# controller.net
KiCad netlist of a schematic drawn in Altium Designer
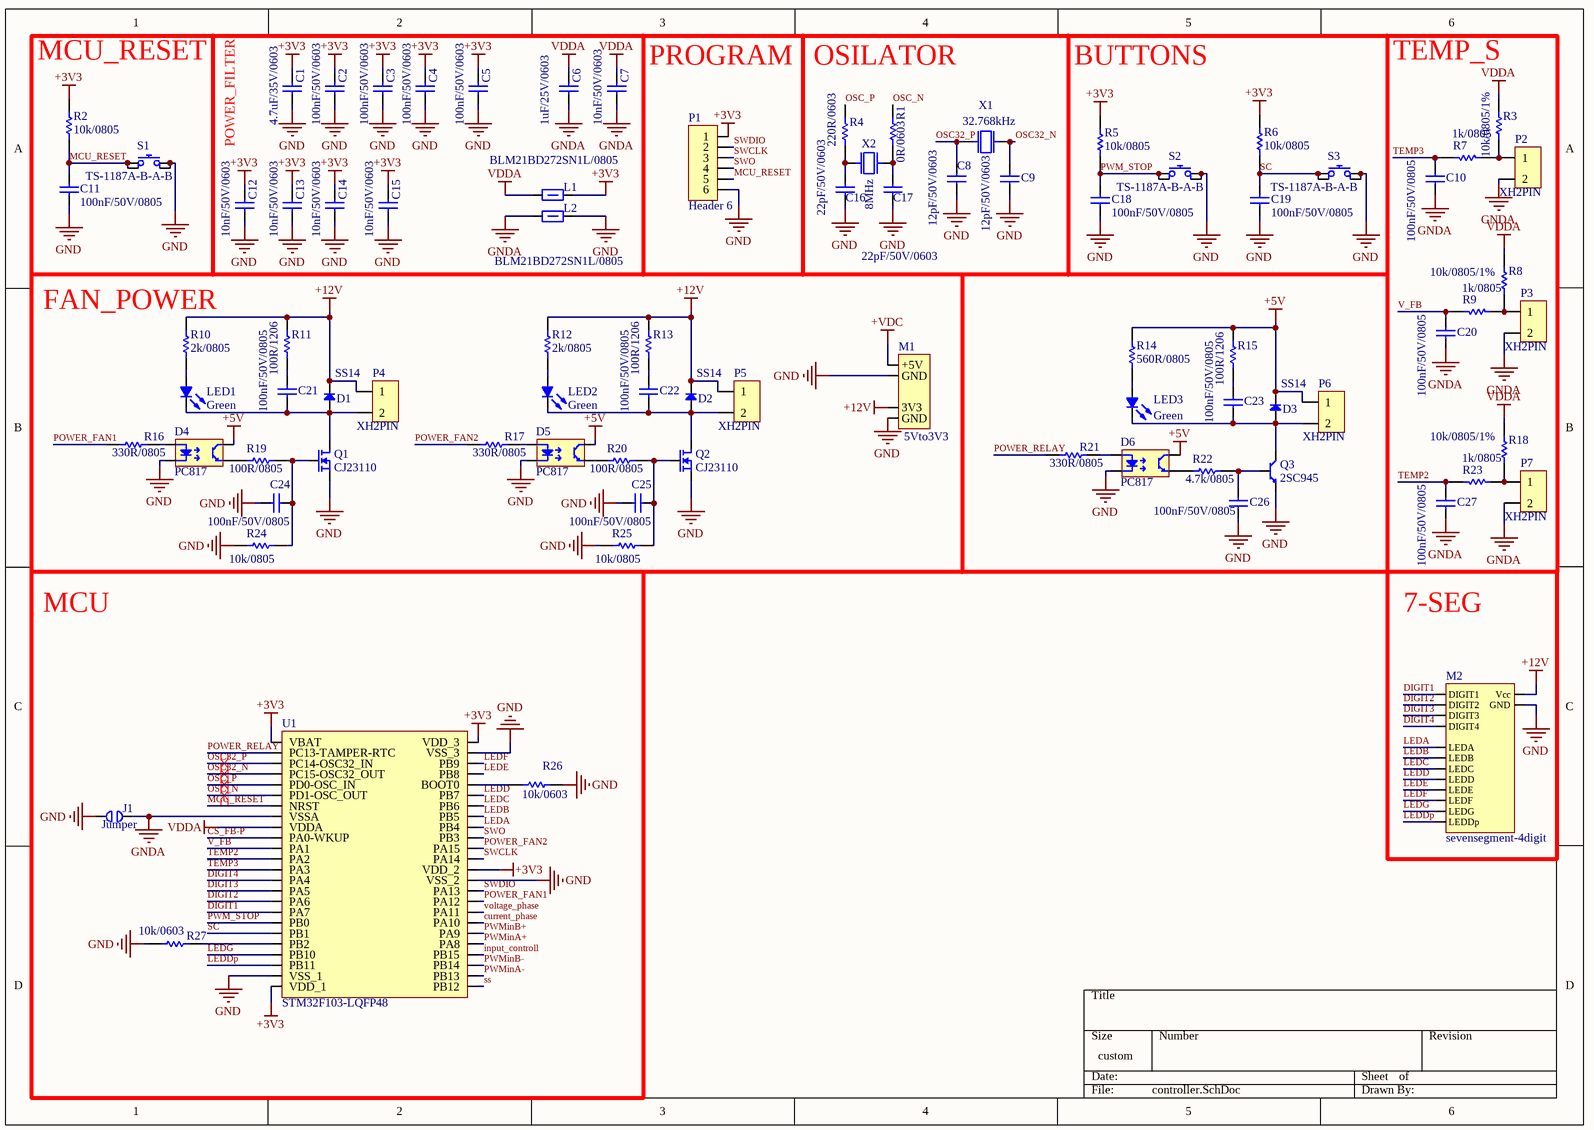
[diagram p0: controller.SchDoc]

(export (version "E")
  (design (tool "Eeschema 10.0.6"))
  (components
    (comp (ref "C1")
      (value "4.7uF/35V/0603")
      (footprint "cap 0603")
      (description "Capacitor")
      (libsource (lib "Schlib") (part "Capacitor"))
    )
    (comp (ref "C2")
      (value "100nF/50V/0603")
      (footprint "cap 0603")
      (description "Capacitor")
      (libsource (lib "Schlib") (part "Capacitor"))
    )
    (comp (ref "C3")
      (value "100nF/50V/0603")
      (footprint "cap 0603")
      (description "Capacitor")
      (libsource (lib "Schlib") (part "Capacitor"))
    )
    (comp (ref "C4")
      (value "100nF/50V/0603")
      (footprint "cap 0603")
      (description "Capacitor")
      (libsource (lib "Schlib") (part "Capacitor"))
    )
    (comp (ref "C5")
      (value "100nF/50V/0603")
      (footprint "cap 0603")
      (description "Capacitor")
      (libsource (lib "Schlib") (part "Capacitor"))
    )
    (comp (ref "C6")
      (value "1uF/25V/0603")
      (footprint "cap 0603")
      (description "Capacitor")
      (libsource (lib "Schlib") (part "Capacitor"))
    )
    (comp (ref "C7")
      (value "10nF/50V/0603")
      (footprint "cap 0603")
      (description "Capacitor")
      (libsource (lib "Schlib") (part "Capacitor"))
    )
    (comp (ref "C8")
      (value "12pF/50V/0603")
      (footprint "cap 0603")
      (description "Capacitor")
      (libsource (lib "Schlib") (part "Capacitor"))
    )
    (comp (ref "C9")
      (value "12pF/50V/0603")
      (footprint "cap 0603")
      (description "Capacitor")
      (libsource (lib "Schlib") (part "Capacitor"))
    )
    (comp (ref "C10")
      (value "100nF/50V/0805")
      (footprint "CAP 0805")
      (description "Capacitor")
      (libsource (lib "Schlib") (part "Capacitor"))
    )
    (comp (ref "C11")
      (value "100nF/50V/0805")
      (footprint "CAP 0805")
      (description "Capacitor")
      (libsource (lib "Schlib") (part "Capacitor"))
    )
    (comp (ref "C12")
      (value "10nF/50V/0603")
      (footprint "cap 0603")
      (description "Capacitor")
      (libsource (lib "Schlib") (part "Capacitor"))
    )
    (comp (ref "C13")
      (value "10nF/50V/0603")
      (footprint "cap 0603")
      (description "Capacitor")
      (libsource (lib "Schlib") (part "Capacitor"))
    )
    (comp (ref "C14")
      (value "10nF/50V/0603")
      (footprint "cap 0603")
      (description "Capacitor")
      (libsource (lib "Schlib") (part "Capacitor"))
    )
    (comp (ref "C15")
      (value "10nF/50V/0603")
      (footprint "cap 0603")
      (description "Capacitor")
      (libsource (lib "Schlib") (part "Capacitor"))
    )
    (comp (ref "C16")
      (value "22pF/50V/0603")
      (footprint "cap 0603")
      (description "Capacitor")
      (libsource (lib "Schlib") (part "Capacitor"))
    )
    (comp (ref "C17")
      (value "22pF/50V/0603")
      (footprint "cap 0603")
      (description "Capacitor")
      (libsource (lib "Schlib") (part "Capacitor"))
    )
    (comp (ref "C18")
      (value "100nF/50V/0805")
      (footprint "CAP 0805")
      (description "Capacitor")
      (libsource (lib "Schlib") (part "Capacitor"))
    )
    (comp (ref "C19")
      (value "100nF/50V/0805")
      (footprint "CAP 0805")
      (description "Capacitor")
      (libsource (lib "Schlib") (part "Capacitor"))
    )
    (comp (ref "C20")
      (value "100nF/50V/0805")
      (footprint "CAP 0805")
      (description "Capacitor")
      (libsource (lib "Schlib") (part "Capacitor"))
    )
    (comp (ref "C21")
      (value "100nF/50V/0805")
      (footprint "CAP 0805")
      (description "Capacitor")
      (libsource (lib "Schlib") (part "Capacitor"))
    )
    (comp (ref "C22")
      (value "100nF/50V/0805")
      (footprint "CAP 0805")
      (description "Capacitor")
      (libsource (lib "Schlib") (part "Capacitor"))
    )
    (comp (ref "C23")
      (value "100nF/50V/0805")
      (footprint "CAP 0805")
      (description "Capacitor")
      (libsource (lib "Schlib") (part "Capacitor"))
    )
    (comp (ref "C24")
      (value "100nF/50V/0805")
      (footprint "CAP 0805")
      (description "Capacitor")
      (libsource (lib "Schlib") (part "Capacitor"))
    )
    (comp (ref "C25")
      (value "100nF/50V/0805")
      (footprint "CAP 0805")
      (description "Capacitor")
      (libsource (lib "Schlib") (part "Capacitor"))
    )
    (comp (ref "C26")
      (value "100nF/50V/0805")
      (footprint "CAP 0805")
      (description "Capacitor")
      (libsource (lib "Schlib") (part "Capacitor"))
    )
    (comp (ref "C27")
      (value "100nF/50V/0805")
      (footprint "CAP 0805")
      (description "Capacitor")
      (libsource (lib "Schlib") (part "Capacitor"))
    )
    (comp (ref "D1") (value "SS14") (footprint "SMA") (libsource (lib "Schlib") (part "Diode")))
    (comp (ref "D2") (value "SS14") (footprint "SMA") (libsource (lib "Schlib") (part "Diode")))
    (comp (ref "D3") (value "SS14") (footprint "SMA") (libsource (lib "Schlib") (part "Diode")))
    (comp (ref "D4") (value "PC817") (footprint "pc817") (libsource (lib "Schlib") (part "PC817")))
    (comp (ref "D5") (value "PC817") (footprint "pc817") (libsource (lib "Schlib") (part "PC817")))
    (comp (ref "D6") (value "PC817") (footprint "pc817") (libsource (lib "Schlib") (part "PC817")))
    (comp (ref "J1") (value "Jumper") (footprint "pin-header 2*1") (libsource (lib "Schlib") (part "Jumper")))
    (comp (ref "L1")
      (value "BLM21BD272SN1L/0805")
      (footprint "RES 0805")
      (libsource (lib "Schlib") (part "Ferrite Bead"))
    )
    (comp (ref "L2")
      (value "BLM21BD272SN1L/0805")
      (footprint "RES 0805")
      (libsource (lib "Schlib") (part "Ferrite Bead"))
    )
    (comp (ref "LED1")
      (value "LED 3mm/Green")
      (footprint "LED 3mm")
      (description "Typical LED")
      (fields (field (name "COLOR") "Green"))
      (libsource (lib "TL494 12V-20A-KARA") (part "LED"))
    )
    (comp (ref "LED2")
      (value "LED 3mm/Green")
      (footprint "LED 3mm")
      (description "Typical LED")
      (fields (field (name "COLOR") "Green"))
      (libsource (lib "TL494 12V-20A-KARA") (part "LED"))
    )
    (comp (ref "LED3")
      (value "LED 3mm/Green")
      (footprint "LED 3mm")
      (description "Typical LED")
      (fields (field (name "COLOR") "Green"))
      (libsource (lib "TL494 12V-20A-KARA") (part "LED"))
    )
    (comp (ref "M1") (value "5Vto3V3") (footprint "5Vto3V3") (libsource (lib "Schlib") (part "5Vto3V3")))
    (comp (ref "M2")
      (value "sevensegment-4digit")
      (footprint "7-SEG-BOARD")
      (libsource (lib "Schlib") (part "sevensegment-4digit"))
    )
    (comp (ref "P1")
      (value "Header 6")
      (footprint "pin-header 6*1")
      (libsource (lib "Schlib") (part "Header 6"))
    )
    (comp (ref "P2")
      (value "XH2PIN")
      (footprint "XH-2Pin")
      (description "RELAY")
      (fields (field (name "PUBLISHER") "Altium Limited"))
      (libsource (lib "Schlib") (part "Header 2H"))
    )
    (comp (ref "P3")
      (value "XH2PIN")
      (footprint "XH-2Pin")
      (description "RELAY")
      (fields (field (name "PUBLISHER") "Altium Limited"))
      (libsource (lib "Schlib") (part "Header 2H"))
    )
    (comp (ref "P4")
      (value "XH2PIN")
      (footprint "XH-2Pin")
      (description "RELAY")
      (fields (field (name "PUBLISHER") "Altium Limited"))
      (libsource (lib "Schlib") (part "Header 2H"))
    )
    (comp (ref "P5")
      (value "XH2PIN")
      (footprint "XH-2Pin")
      (description "RELAY")
      (fields (field (name "PUBLISHER") "Altium Limited"))
      (libsource (lib "Schlib") (part "Header 2H"))
    )
    (comp (ref "P6")
      (value "XH2PIN")
      (footprint "pin-header 2*1")
      (description "RELAY")
      (fields (field (name "PUBLISHER") "Altium Limited"))
      (libsource (lib "Schlib") (part "Header 2H"))
    )
    (comp (ref "P7")
      (value "XH2PIN")
      (footprint "XH-2Pin")
      (description "RELAY")
      (fields (field (name "PUBLISHER") "Altium Limited"))
      (libsource (lib "Schlib") (part "Header 2H"))
    )
    (comp (ref "Q1")
      (value "CJ23110")
      (footprint "SOT-23")
      (libsource (lib "Schlib") (part "Mosfet N-channel"))
    )
    (comp (ref "Q2")
      (value "CJ23110")
      (footprint "SOT-23")
      (libsource (lib "Schlib") (part "Mosfet N-channel"))
    )
    (comp (ref "Q3") (value "2SC945") (footprint "SOT-23") (libsource (lib "Schlib") (part "BJT-NPN")))
    (comp (ref "R1") (value "0R/0603") (footprint "Resistor 0603") (libsource (lib "22") (part "Res 0.5 W")))
    (comp (ref "R2") (value "10k/0805") (footprint "RES 0805") (libsource (lib "22") (part "Res 0.5 W")))
    (comp (ref "R3") (value "10k/0805/1%") (footprint "RES 0805") (libsource (lib "22") (part "Res 0.5 W")))
    (comp (ref "R4")
      (value "220R/0603")
      (footprint "Resistor 0603")
      (libsource (lib "22") (part "Res 0.5 W"))
    )
    (comp (ref "R5") (value "10k/0805") (footprint "RES 0805") (libsource (lib "22") (part "Res 0.5 W")))
    (comp (ref "R6") (value "10k/0805") (footprint "RES 0805") (libsource (lib "22") (part "Res 0.5 W")))
    (comp (ref "R7")
      (value "1k/0805")
      (footprint "RES 0805")
      (description "Resistor")
      (fields (field (name "PUBLISHER") "Altium Limited"))
      (libsource (lib "Miscellaneous Devices") (part "Res1"))
    )
    (comp (ref "R8") (value "10k/0805/1%") (footprint "RES 0805") (libsource (lib "22") (part "Res 0.5 W")))
    (comp (ref "R9")
      (value "1k/0805")
      (footprint "RES 0805")
      (description "Resistor")
      (fields (field (name "PUBLISHER") "Altium Limited"))
      (libsource (lib "Miscellaneous Devices") (part "Res1"))
    )
    (comp (ref "R10") (value "2k/0805") (footprint "RES 0805") (libsource (lib "Schlib") (part "Res")))
    (comp (ref "R11") (value "100R/1206") (footprint "RES 1206") (libsource (lib "22") (part "Res 0.5 W")))
    (comp (ref "R12") (value "2k/0805") (footprint "RES 0805") (libsource (lib "Schlib") (part "Res")))
    (comp (ref "R13") (value "100R/1206") (footprint "RES 1206") (libsource (lib "22") (part "Res 0.5 W")))
    (comp (ref "R14") (value "560R/0805") (footprint "RES 0805") (libsource (lib "Schlib") (part "Res")))
    (comp (ref "R15") (value "100R/1206") (footprint "RES 1206") (libsource (lib "22") (part "Res 0.5 W")))
    (comp (ref "R16") (value "330R/0805") (footprint "RES 0805") (libsource (lib "22") (part "Res 0.5 W")))
    (comp (ref "R17") (value "330R/0805") (footprint "RES 0805") (libsource (lib "22") (part "Res 0.5 W")))
    (comp (ref "R18") (value "10k/0805/1%") (footprint "RES 0805") (libsource (lib "22") (part "Res 0.5 W")))
    (comp (ref "R19") (value "100R/0805") (footprint "RES 0805") (libsource (lib "22") (part "Res 0.5 W")))
    (comp (ref "R20") (value "100R/0805") (footprint "RES 0805") (libsource (lib "22") (part "Res 0.5 W")))
    (comp (ref "R21") (value "330R/0805") (footprint "RES 0805") (libsource (lib "22") (part "Res 0.5 W")))
    (comp (ref "R22") (value "4.7k/0805") (footprint "RES 0805") (libsource (lib "22") (part "Res 0.5 W")))
    (comp (ref "R23")
      (value "1k/0805")
      (footprint "RES 0805")
      (description "Resistor")
      (fields (field (name "PUBLISHER") "Altium Limited"))
      (libsource (lib "Miscellaneous Devices") (part "Res1"))
    )
    (comp (ref "R24") (value "10k/0805") (footprint "RES 0805") (libsource (lib "22") (part "Res 0.5 W")))
    (comp (ref "R25") (value "10k/0805") (footprint "RES 0805") (libsource (lib "22") (part "Res 0.5 W")))
    (comp (ref "R26")
      (value "10k/0603")
      (footprint "Resistor 0603")
      (libsource (lib "22") (part "Res 0.5 W"))
    )
    (comp (ref "R27")
      (value "10k/0603")
      (footprint "Resistor 0603")
      (libsource (lib "22") (part "Res 0.5 W"))
    )
    (comp (ref "S1")
      (value "TS-1187A-B-A-B")
      (footprint "TS-1187A-B-A-B(push button)")
      (libsource (lib "Schlib") (part "push button"))
    )
    (comp (ref "S2")
      (value "TS-1187A-B-A-B")
      (footprint "TS-1187A-B-A-B(push button)")
      (libsource (lib "Schlib") (part "push button"))
    )
    (comp (ref "S3")
      (value "TS-1187A-B-A-B")
      (footprint "TS-1187A-B-A-B(push button)")
      (libsource (lib "Schlib") (part "push button"))
    )
    (comp (ref "U1")
      (value "STM32F103-LQFP48")
      (footprint "LQFP48")
      (libsource (lib "Schlib") (part "STM32F103C8T6"))
    )
    (comp (ref "X1")
      (value "32.768kHz")
      (footprint "CRYSTAL(32.768)-SMD")
      (libsource (lib "Schlib") (part "crystal"))
    )
    (comp (ref "X2") (value "8MHz") (footprint "crystal(8M)-smd") (libsource (lib "Schlib") (part "crystal")))
  )
  (nets
    (net (code "1") (name "+3V3") (class "Default")
      (node (ref "C1") (pin "1") (pinfunction "+_1") (pintype "passive"))
      (node (ref "C12") (pin "2") (pinfunction "-_2") (pintype "passive"))
      (node (ref "C13") (pin "2") (pinfunction "-_2") (pintype "passive"))
      (node (ref "C14") (pin "1") (pinfunction "+_1") (pintype "passive"))
      (node (ref "C15") (pin "2") (pinfunction "-_2") (pintype "passive"))
      (node (ref "C2") (pin "2") (pinfunction "-_2") (pintype "passive"))
      (node (ref "C3") (pin "2") (pinfunction "-_2") (pintype "passive"))
      (node (ref "C4") (pin "1") (pinfunction "+_1") (pintype "passive"))
      (node (ref "C5") (pin "2") (pinfunction "-_2") (pintype "passive"))
      (node (ref "L1") (pin "2") (pinfunction "2_2") (pintype "passive"))
      (node (ref "P1") (pin "1") (pinfunction "1_1") (pintype "passive"))
      (node (ref "R2") (pin "1") (pinfunction "1_1") (pintype "passive"))
      (node (ref "R5") (pin "1") (pinfunction "1_1") (pintype "passive"))
      (node (ref "R6") (pin "1") (pinfunction "1_1") (pintype "passive"))
      (node (ref "U1") (pin "1") (pinfunction "VBAT_1") (pintype "passive"))
      (node (ref "U1") (pin "24") (pinfunction "VDD_1_24") (pintype "passive"))
      (node (ref "U1") (pin "36") (pinfunction "VDD_2_36") (pintype "passive"))
      (node (ref "U1") (pin "48") (pinfunction "VDD_3_48") (pintype "passive"))
    )
    (net (code "2") (name "+5V") (class "Default")
      (node (ref "D3") (pin "2") (pinfunction "2_2") (pintype "passive"))
      (node (ref "D4") (pin "4") (pinfunction "Collector_4") (pintype "passive"))
      (node (ref "D5") (pin "4") (pinfunction "Collector_4") (pintype "passive"))
      (node (ref "D6") (pin "4") (pinfunction "Collector_4") (pintype "passive"))
      (node (ref "P6") (pin "1") (pinfunction "1_1") (pintype "passive"))
      (node (ref "R14") (pin "2") (pinfunction "2_2") (pintype "passive"))
      (node (ref "R15") (pin "1") (pinfunction "1_1") (pintype "passive"))
    )
    (net (code "3") (name "+12V") (class "Default")
      (node (ref "D1") (pin "2") (pinfunction "2_2") (pintype "passive"))
      (node (ref "D2") (pin "2") (pinfunction "2_2") (pintype "passive"))
      (node (ref "M1") (pin "3") (pinfunction "3V3_3") (pintype "passive"))
      (node (ref "M2") (pin "13") (pinfunction "Vcc_13") (pintype "passive"))
      (node (ref "P4") (pin "1") (pinfunction "1_1") (pintype "passive"))
      (node (ref "P5") (pin "1") (pinfunction "1_1") (pintype "passive"))
      (node (ref "R10") (pin "2") (pinfunction "2_2") (pintype "passive"))
      (node (ref "R11") (pin "1") (pinfunction "1_1") (pintype "passive"))
      (node (ref "R12") (pin "2") (pinfunction "2_2") (pintype "passive"))
      (node (ref "R13") (pin "1") (pinfunction "1_1") (pintype "passive"))
    )
    (net (code "4") (name "+VDC") (class "Default")
      (node (ref "M1") (pin "1") (pinfunction "+5V_1") (pintype "passive"))
    )
    (net (code "5") (name "/CS_FB-P") (class "Default")
      (node (ref "U1") (pin "10") (pinfunction "PA0-WKUP_10") (pintype "passive"))
    )
    (net (code "6") (name "/DIGIT1") (class "Default")
      (node (ref "M2") (pin "1") (pinfunction "DIGIT1_1") (pintype "passive"))
      (node (ref "U1") (pin "17") (pinfunction "PA7_17") (pintype "passive"))
    )
    (net (code "7") (name "/DIGIT2") (class "Default")
      (node (ref "M2") (pin "2") (pinfunction "DIGIT2_2") (pintype "passive"))
      (node (ref "U1") (pin "16") (pinfunction "PA6_16") (pintype "passive"))
    )
    (net (code "8") (name "/DIGIT3") (class "Default")
      (node (ref "M2") (pin "3") (pinfunction "DIGIT3_3") (pintype "passive"))
      (node (ref "U1") (pin "15") (pinfunction "PA5_15") (pintype "passive"))
    )
    (net (code "9") (name "/DIGIT4") (class "Default")
      (node (ref "M2") (pin "4") (pinfunction "DIGIT4_4") (pintype "passive"))
      (node (ref "U1") (pin "14") (pinfunction "PA4_14") (pintype "passive"))
    )
    (net (code "10") (name "/LEDA") (class "Default")
      (node (ref "M2") (pin "5") (pinfunction "LEDA_5") (pintype "passive"))
      (node (ref "U1") (pin "40") (pinfunction "PB4_40") (pintype "passive"))
    )
    (net (code "11") (name "/LEDB") (class "Default")
      (node (ref "M2") (pin "6") (pinfunction "LEDB_6") (pintype "passive"))
      (node (ref "U1") (pin "41") (pinfunction "PB5_41") (pintype "passive"))
    )
    (net (code "12") (name "/LEDC") (class "Default")
      (node (ref "M2") (pin "7") (pinfunction "LEDC_7") (pintype "passive"))
      (node (ref "U1") (pin "42") (pinfunction "PB6_42") (pintype "passive"))
    )
    (net (code "13") (name "/LEDD") (class "Default")
      (node (ref "M2") (pin "8") (pinfunction "LEDD_8") (pintype "passive"))
      (node (ref "U1") (pin "43") (pinfunction "PB7_43") (pintype "passive"))
    )
    (net (code "14") (name "/LEDDp") (class "Default")
      (node (ref "M2") (pin "12") (pinfunction "LEDDp_12") (pintype "passive"))
      (node (ref "U1") (pin "22") (pinfunction "PB11_22") (pintype "passive"))
    )
    (net (code "15") (name "/LEDE") (class "Default")
      (node (ref "M2") (pin "9") (pinfunction "LEDE_9") (pintype "passive"))
      (node (ref "U1") (pin "45") (pinfunction "PB8_45") (pintype "passive"))
    )
    (net (code "16") (name "/LEDF") (class "Default")
      (node (ref "M2") (pin "10") (pinfunction "LEDF_10") (pintype "passive"))
      (node (ref "U1") (pin "46") (pinfunction "PB9_46") (pintype "passive"))
    )
    (net (code "17") (name "/LEDG") (class "Default")
      (node (ref "M2") (pin "11") (pinfunction "LEDG_11") (pintype "passive"))
      (node (ref "U1") (pin "21") (pinfunction "PB10_21") (pintype "passive"))
    )
    (net (code "18") (name "/MCU_RESET") (class "Default")
      (node (ref "C11") (pin "2") (pinfunction "-_2") (pintype "passive"))
      (node (ref "P1") (pin "5") (pinfunction "5_5") (pintype "passive"))
      (node (ref "R2") (pin "2") (pinfunction "2_2") (pintype "passive"))
      (node (ref "S1") (pin "1") (pinfunction "1_1") (pintype "passive"))
      (node (ref "S1") (pin "4") (pinfunction "4_4") (pintype "passive"))
      (node (ref "U1") (pin "7") (pinfunction "NRST_7") (pintype "passive"))
    )
    (net (code "19") (name "/OSC32_N") (class "Default")
      (node (ref "C9") (pin "2") (pinfunction "-_2") (pintype "passive"))
      (node (ref "U1") (pin "4") (pinfunction "PC15-OSC32_OUT_4") (pintype "passive"))
      (node (ref "X1") (pin "2") (pinfunction "2_2") (pintype "passive"))
    )
    (net (code "20") (name "/OSC32_P") (class "Default")
      (node (ref "C8") (pin "2") (pinfunction "-_2") (pintype "passive"))
      (node (ref "U1") (pin "3") (pinfunction "PC14-OSC32_IN_3") (pintype "passive"))
      (node (ref "X1") (pin "1") (pinfunction "1_1") (pintype "passive"))
    )
    (net (code "21") (name "/OSC_N") (class "Default")
      (node (ref "R1") (pin "1") (pinfunction "1_1") (pintype "passive"))
      (node (ref "U1") (pin "6") (pinfunction "PD1-OSC_OUT_6") (pintype "passive"))
    )
    (net (code "22") (name "/OSC_P") (class "Default")
      (node (ref "R4") (pin "1") (pinfunction "1_1") (pintype "passive"))
      (node (ref "U1") (pin "5") (pinfunction "PD0-OSC_IN_5") (pintype "passive"))
    )
    (net (code "23") (name "/POWER_FAN1") (class "Default")
      (node (ref "R16") (pin "2") (pinfunction "2_2") (pintype "passive"))
      (node (ref "U1") (pin "33") (pinfunction "PA12_33") (pintype "passive"))
    )
    (net (code "24") (name "/POWER_FAN2") (class "Default")
      (node (ref "R17") (pin "2") (pinfunction "2_2") (pintype "passive"))
      (node (ref "U1") (pin "38") (pinfunction "PA15_38") (pintype "passive"))
    )
    (net (code "25") (name "/POWER_RELAY") (class "Default")
      (node (ref "R21") (pin "2") (pinfunction "2_2") (pintype "passive"))
      (node (ref "U1") (pin "2") (pinfunction "PC13-TAMPER-RTC_2") (pintype "passive"))
    )
    (net (code "26") (name "/PWM_STOP") (class "Default")
      (node (ref "C18") (pin "2") (pinfunction "-_2") (pintype "passive"))
      (node (ref "R5") (pin "2") (pinfunction "2_2") (pintype "passive"))
      (node (ref "S2") (pin "1") (pinfunction "1_1") (pintype "passive"))
      (node (ref "S2") (pin "4") (pinfunction "4_4") (pintype "passive"))
      (node (ref "U1") (pin "18") (pinfunction "PB0_18") (pintype "passive"))
    )
    (net (code "27") (name "/PWMinA+") (class "Default")
      (node (ref "U1") (pin "29") (pinfunction "PA8_29") (pintype "passive"))
    )
    (net (code "28") (name "/PWMinA-") (class "Default")
      (node (ref "U1") (pin "26") (pinfunction "PB13_26") (pintype "passive"))
    )
    (net (code "29") (name "/PWMinB+") (class "Default")
      (node (ref "U1") (pin "30") (pinfunction "PA9_30") (pintype "passive"))
    )
    (net (code "30") (name "/PWMinB-") (class "Default")
      (node (ref "U1") (pin "27") (pinfunction "PB14_27") (pintype "passive"))
    )
    (net (code "31") (name "/SC") (class "Default")
      (node (ref "C19") (pin "2") (pinfunction "-_2") (pintype "passive"))
      (node (ref "R6") (pin "2") (pinfunction "2_2") (pintype "passive"))
      (node (ref "S3") (pin "1") (pinfunction "1_1") (pintype "passive"))
      (node (ref "S3") (pin "4") (pinfunction "4_4") (pintype "passive"))
      (node (ref "U1") (pin "19") (pinfunction "PB1_19") (pintype "passive"))
    )
    (net (code "32") (name "/SWCLK") (class "Default")
      (node (ref "P1") (pin "3") (pinfunction "3_3") (pintype "passive"))
      (node (ref "U1") (pin "37") (pinfunction "PA14_37") (pintype "passive"))
    )
    (net (code "33") (name "/SWDIO") (class "Default")
      (node (ref "P1") (pin "2") (pinfunction "2_2") (pintype "passive"))
      (node (ref "U1") (pin "34") (pinfunction "PA13_34") (pintype "passive"))
    )
    (net (code "34") (name "/SWO") (class "Default")
      (node (ref "P1") (pin "4") (pinfunction "4_4") (pintype "passive"))
      (node (ref "U1") (pin "39") (pinfunction "PB3_39") (pintype "passive"))
    )
    (net (code "35") (name "/TEMP2") (class "Default")
      (node (ref "C27") (pin "1") (pinfunction "+_1") (pintype "passive"))
      (node (ref "R23") (pin "2") (pinfunction "2_2") (pintype "passive"))
      (node (ref "U1") (pin "12") (pinfunction "PA2_12") (pintype "passive"))
    )
    (net (code "36") (name "/TEMP3") (class "Default")
      (node (ref "C10") (pin "1") (pinfunction "+_1") (pintype "passive"))
      (node (ref "R7") (pin "2") (pinfunction "2_2") (pintype "passive"))
      (node (ref "U1") (pin "13") (pinfunction "PA3_13") (pintype "passive"))
    )
    (net (code "37") (name "/V_FB") (class "Default")
      (node (ref "C20") (pin "1") (pinfunction "+_1") (pintype "passive"))
      (node (ref "R9") (pin "2") (pinfunction "2_2") (pintype "passive"))
      (node (ref "U1") (pin "11") (pinfunction "PA1_11") (pintype "passive"))
    )
    (net (code "38") (name "/current_phase") (class "Default")
      (node (ref "U1") (pin "31") (pinfunction "PA10_31") (pintype "passive"))
    )
    (net (code "39") (name "/input_controll") (class "Default")
      (node (ref "U1") (pin "28") (pinfunction "PB15_28") (pintype "passive"))
    )
    (net (code "40") (name "/ss") (class "Default")
      (node (ref "U1") (pin "25") (pinfunction "PB12_25") (pintype "passive"))
    )
    (net (code "41") (name "/voltage_phase") (class "Default")
      (node (ref "U1") (pin "32") (pinfunction "PA11_32") (pintype "passive"))
    )
    (net (code "42") (name "GND") (class "Default")
      (node (ref "C1") (pin "2") (pinfunction "-_2") (pintype "passive"))
      (node (ref "C11") (pin "1") (pinfunction "+_1") (pintype "passive"))
      (node (ref "C12") (pin "1") (pinfunction "+_1") (pintype "passive"))
      (node (ref "C13") (pin "1") (pinfunction "+_1") (pintype "passive"))
      (node (ref "C14") (pin "2") (pinfunction "-_2") (pintype "passive"))
      (node (ref "C15") (pin "1") (pinfunction "+_1") (pintype "passive"))
      (node (ref "C16") (pin "1") (pinfunction "+_1") (pintype "passive"))
      (node (ref "C17") (pin "1") (pinfunction "+_1") (pintype "passive"))
      (node (ref "C18") (pin "1") (pinfunction "+_1") (pintype "passive"))
      (node (ref "C19") (pin "1") (pinfunction "+_1") (pintype "passive"))
      (node (ref "C2") (pin "1") (pinfunction "+_1") (pintype "passive"))
      (node (ref "C24") (pin "1") (pinfunction "+_1") (pintype "passive"))
      (node (ref "C25") (pin "1") (pinfunction "+_1") (pintype "passive"))
      (node (ref "C26") (pin "1") (pinfunction "+_1") (pintype "passive"))
      (node (ref "C3") (pin "1") (pinfunction "+_1") (pintype "passive"))
      (node (ref "C4") (pin "2") (pinfunction "-_2") (pintype "passive"))
      (node (ref "C5") (pin "1") (pinfunction "+_1") (pintype "passive"))
      (node (ref "C8") (pin "1") (pinfunction "+_1") (pintype "passive"))
      (node (ref "C9") (pin "1") (pinfunction "+_1") (pintype "passive"))
      (node (ref "D4") (pin "2") (pinfunction "Cathode_2") (pintype "passive"))
      (node (ref "D5") (pin "2") (pinfunction "Cathode_2") (pintype "passive"))
      (node (ref "D6") (pin "2") (pinfunction "Cathode_2") (pintype "passive"))
      (node (ref "J1") (pin "1") (pinfunction "1_1") (pintype "passive"))
      (node (ref "L2") (pin "2") (pinfunction "2_2") (pintype "passive"))
      (node (ref "M1") (pin "2") (pinfunction "GND_2") (pintype "passive"))
      (node (ref "M1") (pin "4") (pinfunction "GND_4") (pintype "passive"))
      (node (ref "M2") (pin "14") (pinfunction "GND_14") (pintype "passive"))
      (node (ref "P1") (pin "6") (pinfunction "6_6") (pintype "passive"))
      (node (ref "Q1") (pin "2") (pinfunction "S_2") (pintype "passive"))
      (node (ref "Q2") (pin "2") (pinfunction "S_2") (pintype "passive"))
      (node (ref "Q3") (pin "2") (pinfunction "E_2") (pintype "passive"))
      (node (ref "R24") (pin "2") (pinfunction "2_2") (pintype "passive"))
      (node (ref "R25") (pin "2") (pinfunction "2_2") (pintype "passive"))
      (node (ref "R26") (pin "2") (pinfunction "2_2") (pintype "passive"))
      (node (ref "R27") (pin "2") (pinfunction "2_2") (pintype "passive"))
      (node (ref "S1") (pin "2") (pinfunction "2_2") (pintype "passive"))
      (node (ref "S1") (pin "3") (pinfunction "3_3") (pintype "passive"))
      (node (ref "S2") (pin "2") (pinfunction "2_2") (pintype "passive"))
      (node (ref "S2") (pin "3") (pinfunction "3_3") (pintype "passive"))
      (node (ref "S3") (pin "2") (pinfunction "2_2") (pintype "passive"))
      (node (ref "S3") (pin "3") (pinfunction "3_3") (pintype "passive"))
      (node (ref "U1") (pin "23") (pinfunction "VSS_1_23") (pintype "passive"))
      (node (ref "U1") (pin "35") (pinfunction "VSS_2_35") (pintype "passive"))
      (node (ref "U1") (pin "47") (pinfunction "VSS_3_47") (pintype "passive"))
    )
    (net (code "43") (name "GNDA") (class "Default")
      (node (ref "C10") (pin "2") (pinfunction "-_2") (pintype "passive"))
      (node (ref "C20") (pin "2") (pinfunction "-_2") (pintype "passive"))
      (node (ref "C27") (pin "2") (pinfunction "-_2") (pintype "passive"))
      (node (ref "C6") (pin "1") (pinfunction "+_1") (pintype "passive"))
      (node (ref "C7") (pin "2") (pinfunction "-_2") (pintype "passive"))
      (node (ref "J1") (pin "2") (pinfunction "2_2") (pintype "passive"))
      (node (ref "L2") (pin "1") (pinfunction "1_1") (pintype "passive"))
      (node (ref "P2") (pin "2") (pinfunction "2_2") (pintype "passive"))
      (node (ref "P3") (pin "2") (pinfunction "2_2") (pintype "passive"))
      (node (ref "P7") (pin "2") (pinfunction "2_2") (pintype "passive"))
      (node (ref "U1") (pin "8") (pinfunction "VSSA_8") (pintype "passive"))
    )
    (net (code "44") (name "Net-(C16--)") (class "Default")
      (node (ref "C16") (pin "2") (pinfunction "-_2") (pintype "passive"))
      (node (ref "R4") (pin "2") (pinfunction "2_2") (pintype "passive"))
      (node (ref "X2") (pin "1") (pinfunction "1_1") (pintype "passive"))
    )
    (net (code "45") (name "Net-(C17--)") (class "Default")
      (node (ref "C17") (pin "2") (pinfunction "-_2") (pintype "passive"))
      (node (ref "R1") (pin "2") (pinfunction "2_2") (pintype "passive"))
      (node (ref "X2") (pin "2") (pinfunction "2_2") (pintype "passive"))
    )
    (net (code "46") (name "Net-(C21-+)") (class "Default")
      (node (ref "C21") (pin "1") (pinfunction "+_1") (pintype "passive"))
      (node (ref "D1") (pin "1") (pinfunction "1_1") (pintype "passive"))
      (node (ref "LED1") (pin "2") (pinfunction "K_2") (pintype "passive"))
      (node (ref "P4") (pin "2") (pinfunction "2_2") (pintype "passive"))
      (node (ref "Q1") (pin "3") (pinfunction "D_3") (pintype "passive"))
    )
    (net (code "47") (name "Net-(C21--)") (class "Default")
      (node (ref "C21") (pin "2") (pinfunction "-_2") (pintype "passive"))
      (node (ref "R11") (pin "2") (pinfunction "2_2") (pintype "passive"))
    )
    (net (code "48") (name "Net-(C22-+)") (class "Default")
      (node (ref "C22") (pin "1") (pinfunction "+_1") (pintype "passive"))
      (node (ref "D2") (pin "1") (pinfunction "1_1") (pintype "passive"))
      (node (ref "LED2") (pin "2") (pinfunction "K_2") (pintype "passive"))
      (node (ref "P5") (pin "2") (pinfunction "2_2") (pintype "passive"))
      (node (ref "Q2") (pin "3") (pinfunction "D_3") (pintype "passive"))
    )
    (net (code "49") (name "Net-(C22--)") (class "Default")
      (node (ref "C22") (pin "2") (pinfunction "-_2") (pintype "passive"))
      (node (ref "R13") (pin "2") (pinfunction "2_2") (pintype "passive"))
    )
    (net (code "50") (name "Net-(C23-+)") (class "Default")
      (node (ref "C23") (pin "1") (pinfunction "+_1") (pintype "passive"))
      (node (ref "D3") (pin "1") (pinfunction "1_1") (pintype "passive"))
      (node (ref "LED3") (pin "2") (pinfunction "K_2") (pintype "passive"))
      (node (ref "P6") (pin "2") (pinfunction "2_2") (pintype "passive"))
      (node (ref "Q3") (pin "3") (pinfunction "C_3") (pintype "passive"))
    )
    (net (code "51") (name "Net-(C23--)") (class "Default")
      (node (ref "C23") (pin "2") (pinfunction "-_2") (pintype "passive"))
      (node (ref "R15") (pin "2") (pinfunction "2_2") (pintype "passive"))
    )
    (net (code "52") (name "Net-(C24--)") (class "Default")
      (node (ref "C24") (pin "2") (pinfunction "-_2") (pintype "passive"))
      (node (ref "Q1") (pin "1") (pinfunction "G_1") (pintype "passive"))
      (node (ref "R19") (pin "1") (pinfunction "1_1") (pintype "passive"))
      (node (ref "R24") (pin "1") (pinfunction "1_1") (pintype "passive"))
    )
    (net (code "53") (name "Net-(C25--)") (class "Default")
      (node (ref "C25") (pin "2") (pinfunction "-_2") (pintype "passive"))
      (node (ref "Q2") (pin "1") (pinfunction "G_1") (pintype "passive"))
      (node (ref "R20") (pin "1") (pinfunction "1_1") (pintype "passive"))
      (node (ref "R25") (pin "1") (pinfunction "1_1") (pintype "passive"))
    )
    (net (code "54") (name "Net-(C26--)") (class "Default")
      (node (ref "C26") (pin "2") (pinfunction "-_2") (pintype "passive"))
      (node (ref "Q3") (pin "1") (pinfunction "B_1") (pintype "passive"))
      (node (ref "R22") (pin "1") (pinfunction "1_1") (pintype "passive"))
    )
    (net (code "55") (name "Net-(D4-Anode)") (class "Default")
      (node (ref "D4") (pin "1") (pinfunction "Anode_1") (pintype "passive"))
      (node (ref "R16") (pin "1") (pinfunction "1_1") (pintype "passive"))
    )
    (net (code "56") (name "Net-(D4-Emitter)") (class "Default")
      (node (ref "D4") (pin "3") (pinfunction "Emitter_3") (pintype "passive"))
      (node (ref "R19") (pin "2") (pinfunction "2_2") (pintype "passive"))
    )
    (net (code "57") (name "Net-(D5-Anode)") (class "Default")
      (node (ref "D5") (pin "1") (pinfunction "Anode_1") (pintype "passive"))
      (node (ref "R17") (pin "1") (pinfunction "1_1") (pintype "passive"))
    )
    (net (code "58") (name "Net-(D5-Emitter)") (class "Default")
      (node (ref "D5") (pin "3") (pinfunction "Emitter_3") (pintype "passive"))
      (node (ref "R20") (pin "2") (pinfunction "2_2") (pintype "passive"))
    )
    (net (code "59") (name "Net-(D6-Anode)") (class "Default")
      (node (ref "D6") (pin "1") (pinfunction "Anode_1") (pintype "passive"))
      (node (ref "R21") (pin "1") (pinfunction "1_1") (pintype "passive"))
    )
    (net (code "60") (name "Net-(D6-Emitter)") (class "Default")
      (node (ref "D6") (pin "3") (pinfunction "Emitter_3") (pintype "passive"))
      (node (ref "R22") (pin "2") (pinfunction "2_2") (pintype "passive"))
    )
    (net (code "61") (name "Net-(LED1-A)") (class "Default")
      (node (ref "LED1") (pin "1") (pinfunction "A_1") (pintype "passive"))
      (node (ref "R10") (pin "1") (pinfunction "1_1") (pintype "passive"))
    )
    (net (code "62") (name "Net-(LED2-A)") (class "Default")
      (node (ref "LED2") (pin "1") (pinfunction "A_1") (pintype "passive"))
      (node (ref "R12") (pin "1") (pinfunction "1_1") (pintype "passive"))
    )
    (net (code "63") (name "Net-(LED3-A)") (class "Default")
      (node (ref "LED3") (pin "1") (pinfunction "A_1") (pintype "passive"))
      (node (ref "R14") (pin "1") (pinfunction "1_1") (pintype "passive"))
    )
    (net (code "64") (name "Net-(P2-Pad1)") (class "Default")
      (node (ref "P2") (pin "1") (pinfunction "1_1") (pintype "passive"))
      (node (ref "R3") (pin "2") (pinfunction "2_2") (pintype "passive"))
      (node (ref "R7") (pin "1") (pinfunction "1_1") (pintype "passive"))
    )
    (net (code "65") (name "Net-(P3-Pad1)") (class "Default")
      (node (ref "P3") (pin "1") (pinfunction "1_1") (pintype "passive"))
      (node (ref "R8") (pin "2") (pinfunction "2_2") (pintype "passive"))
      (node (ref "R9") (pin "1") (pinfunction "1_1") (pintype "passive"))
    )
    (net (code "66") (name "Net-(P7-Pad1)") (class "Default")
      (node (ref "P7") (pin "1") (pinfunction "1_1") (pintype "passive"))
      (node (ref "R18") (pin "2") (pinfunction "2_2") (pintype "passive"))
      (node (ref "R23") (pin "1") (pinfunction "1_1") (pintype "passive"))
    )
    (net (code "67") (name "Net-(U1-BOOT0)") (class "Default")
      (node (ref "R26") (pin "1") (pinfunction "1_1") (pintype "passive"))
      (node (ref "U1") (pin "44") (pinfunction "BOOT0_44") (pintype "passive"))
    )
    (net (code "68") (name "Net-(U1-PB2)") (class "Default")
      (node (ref "R27") (pin "1") (pinfunction "1_1") (pintype "passive"))
      (node (ref "U1") (pin "20") (pinfunction "PB2_20") (pintype "passive"))
    )
    (net (code "69") (name "VDDA") (class "Default")
      (node (ref "C6") (pin "2") (pinfunction "-_2") (pintype "passive"))
      (node (ref "C7") (pin "1") (pinfunction "+_1") (pintype "passive"))
      (node (ref "L1") (pin "1") (pinfunction "1_1") (pintype "passive"))
      (node (ref "R18") (pin "1") (pinfunction "1_1") (pintype "passive"))
      (node (ref "R3") (pin "1") (pinfunction "1_1") (pintype "passive"))
      (node (ref "R8") (pin "1") (pinfunction "1_1") (pintype "passive"))
      (node (ref "U1") (pin "9") (pinfunction "VDDA_9") (pintype "passive"))
    )
  )
)
